# SP6205.net
KiCad netlist of a schematic drawn in Altium Designer
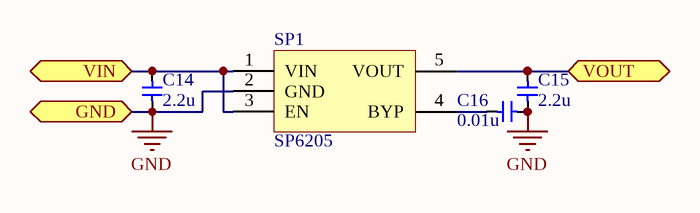
[diagram p0: SP6205.SchDoc]

(export (version "E")
  (design (tool "Eeschema 10.0.6"))
  (components
    (comp (ref "C14")
      (value "2.2u")
      (footprint "CAP_0603")
      (description "Capacitor")
      (fields (field (name "Comment") "Cap_0603"))
      (libsource (lib "SCH_Passive") (part "Cap_0603"))
    )
    (comp (ref "C15")
      (value "2.2u")
      (footprint "CAP_0603")
      (description "Capacitor")
      (fields (field (name "Comment") "Cap_0603"))
      (libsource (lib "SCH_Passive") (part "Cap_0603"))
    )
    (comp (ref "C16")
      (value "0.01u")
      (footprint "CAP_0603")
      (description "Capacitor")
      (fields (field (name "Comment") "Cap_0603"))
      (libsource (lib "SCH_Passive") (part "Cap_0603"))
    )
    (comp (ref "SP1")
      (value "SP6205")
      (footprint "SOT23-5")
      (description "Power")
      (libsource (lib "SCH_IntegratedCircuit") (part "SP6205"))
    )
  )
  (nets
    (net (code "1") (name "/VIN") (class "Default")
      (node (ref "C14") (pin "2") (pinfunction "2_2") (pintype "passive"))
      (node (ref "SP1") (pin "1") (pinfunction "VIN_1") (pintype "passive"))
      (node (ref "SP1") (pin "3") (pinfunction "EN_3") (pintype "power_in"))
    )
    (net (code "2") (name "/VOUT") (class "Default")
      (node (ref "C15") (pin "2") (pinfunction "2_2") (pintype "passive"))
      (node (ref "SP1") (pin "5") (pinfunction "VOUT_5") (pintype "passive"))
    )
    (net (code "3") (name "GND") (class "Default")
      (node (ref "C14") (pin "1") (pinfunction "1_1") (pintype "passive"))
      (node (ref "C15") (pin "1") (pinfunction "1_1") (pintype "passive"))
      (node (ref "C16") (pin "1") (pinfunction "1_1") (pintype "passive"))
      (node (ref "SP1") (pin "2") (pinfunction "GND_2") (pintype "passive"))
    )
    (net (code "4") (name "Net-(SP1-BYP)") (class "Default")
      (node (ref "C16") (pin "2") (pinfunction "2_2") (pintype "passive"))
      (node (ref "SP1") (pin "4") (pinfunction "BYP_4") (pintype "passive"))
    )
  )
)
